# mag_mpu.net
KiCad netlist of a schematic drawn in Altium Designer
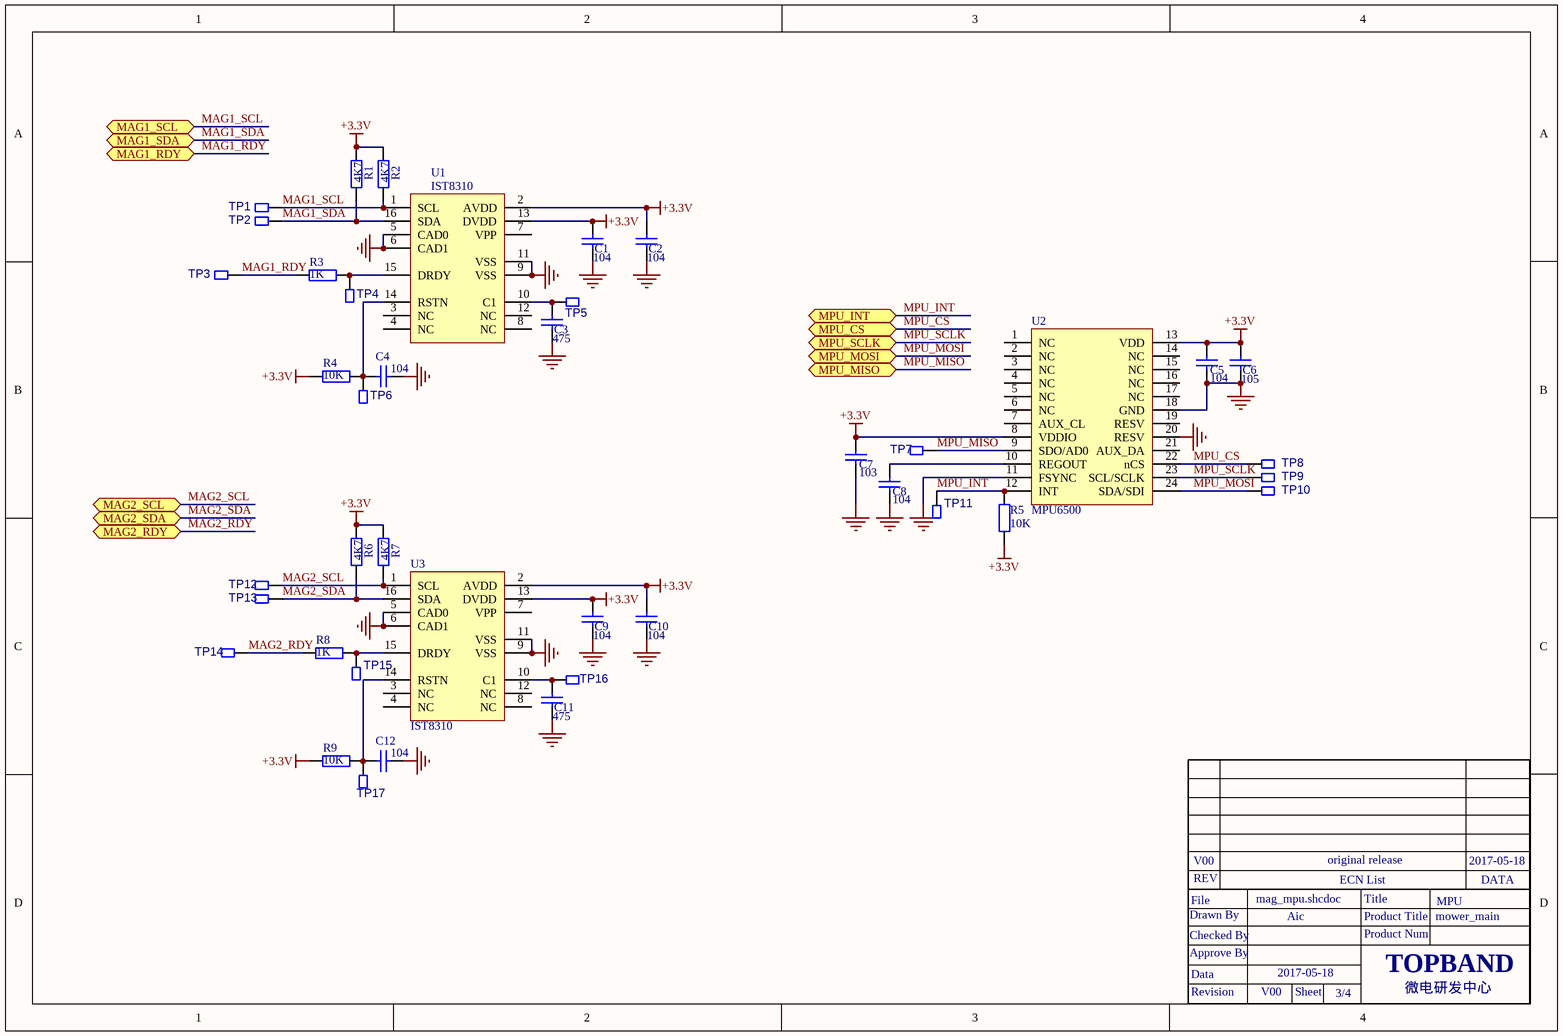
[diagram p0: mag_mpu.SchDoc]

(export (version "E")
  (design (tool "Eeschema 10.0.6"))
  (components
    (comp (ref "C1")
      (value "104")
      (footprint "0603C")
      (libsource (lib "altium-import") (part "root_1_Cap(0603)_"))
    )
    (comp (ref "C2")
      (value "104")
      (footprint "0603C")
      (libsource (lib "altium-import") (part "root_1_Cap(0603)_"))
    )
    (comp (ref "C3")
      (value "475")
      (footprint "0603C")
      (libsource (lib "altium-import") (part "root_1_Cap(0603)_"))
    )
    (comp (ref "C4")
      (value "104")
      (footprint "0603C")
      (libsource (lib "altium-import") (part "root_2_Cap(0603)_"))
    )
    (comp (ref "C5")
      (value "104")
      (footprint "0603C")
      (libsource (lib "altium-import") (part "root_1_Cap(0603)_"))
    )
    (comp (ref "C6")
      (value "105")
      (footprint "0603C")
      (libsource (lib "altium-import") (part "root_1_Cap(0603)_"))
    )
    (comp (ref "C7")
      (value "103")
      (footprint "0603C")
      (libsource (lib "altium-import") (part "root_1_Cap(0603)_"))
    )
    (comp (ref "C8")
      (value "104")
      (footprint "0603C")
      (libsource (lib "altium-import") (part "root_1_Cap(0603)_"))
    )
    (comp (ref "C9")
      (value "104")
      (footprint "0603C")
      (libsource (lib "altium-import") (part "root_1_Cap(0603)_"))
    )
    (comp (ref "C10")
      (value "104")
      (footprint "0603C")
      (libsource (lib "altium-import") (part "root_1_Cap(0603)_"))
    )
    (comp (ref "C11")
      (value "475")
      (footprint "0603C")
      (libsource (lib "altium-import") (part "root_1_Cap(0603)_"))
    )
    (comp (ref "C12")
      (value "104")
      (footprint "0603C")
      (libsource (lib "altium-import") (part "root_2_Cap(0603)_"))
    )
    (comp (ref "R1")
      (value "4K7")
      (footprint "0603R")
      (description "Resistor")
      (fields (field (name "PUBLISHER") "Altium Limited"))
      (libsource (lib "") (part "Res2_1"))
    )
    (comp (ref "R2")
      (value "4K7")
      (footprint "0603R")
      (description "Resistor")
      (fields (field (name "PUBLISHER") "Altium Limited"))
      (libsource (lib "") (part "Res2_1"))
    )
    (comp (ref "R3")
      (value "1K")
      (footprint "0603R")
      (description "Resistor")
      (fields (field (name "PUBLISHER") "Altium Limited"))
      (libsource (lib "Miscellaneous Devices") (part "Res2"))
    )
    (comp (ref "R4")
      (value "10K")
      (footprint "0603R")
      (description "Resistor")
      (fields (field (name "PUBLISHER") "Altium Limited"))
      (libsource (lib "") (part "Res2_2"))
    )
    (comp (ref "R5")
      (value "10K")
      (footprint "0603R")
      (description "Resistor")
      (fields (field (name "PUBLISHER") "Altium Limited"))
      (libsource (lib "") (part "Res2_3"))
    )
    (comp (ref "R6")
      (value "4K7")
      (footprint "0603R")
      (description "Resistor")
      (fields (field (name "PUBLISHER") "Altium Limited"))
      (libsource (lib "") (part "Res2_1"))
    )
    (comp (ref "R7")
      (value "4K7")
      (footprint "0603R")
      (description "Resistor")
      (fields (field (name "PUBLISHER") "Altium Limited"))
      (libsource (lib "") (part "Res2_1"))
    )
    (comp (ref "R8")
      (value "1K")
      (footprint "0603R")
      (description "Resistor")
      (fields (field (name "PUBLISHER") "Altium Limited"))
      (libsource (lib "Miscellaneous Devices") (part "Res2"))
    )
    (comp (ref "R9")
      (value "10K")
      (footprint "0603R")
      (description "Resistor")
      (fields (field (name "PUBLISHER") "Altium Limited"))
      (libsource (lib "") (part "Res2_2"))
    )
    (comp (ref "TP1") (value "TP") (footprint "TEST-0.8MM") (libsource (lib "Topband1") (part "TP")))
    (comp (ref "TP2") (value "TP") (footprint "TEST-0.8MM") (libsource (lib "Topband1") (part "TP")))
    (comp (ref "TP3") (value "TP") (footprint "TEST-0.8MM") (libsource (lib "Topband1") (part "TP")))
    (comp (ref "TP4") (value "TP") (footprint "TEST-0.8MM") (libsource (lib "Topband1") (part "TP")))
    (comp (ref "TP5") (value "TP") (footprint "TEST-0.8MM") (libsource (lib "Topband1") (part "TP")))
    (comp (ref "TP6") (value "TP") (footprint "TEST-0.8MM") (libsource (lib "Topband1") (part "TP")))
    (comp (ref "TP7") (value "TP") (footprint "TEST-0.8MM") (libsource (lib "Topband1") (part "TP")))
    (comp (ref "TP8") (value "TP") (footprint "TEST-0.8MM") (libsource (lib "Topband1") (part "TP")))
    (comp (ref "TP9") (value "TP") (footprint "TEST-0.8MM") (libsource (lib "Topband1") (part "TP")))
    (comp (ref "TP10") (value "TP") (footprint "TEST-0.8MM") (libsource (lib "Topband1") (part "TP")))
    (comp (ref "TP11") (value "TP") (footprint "TEST-0.8MM") (libsource (lib "Topband1") (part "TP")))
    (comp (ref "TP12") (value "TP") (footprint "TEST-0.8MM") (libsource (lib "Topband1") (part "TP")))
    (comp (ref "TP13") (value "TP") (footprint "TEST-0.8MM") (libsource (lib "Topband1") (part "TP")))
    (comp (ref "TP14") (value "TP") (footprint "TEST-0.8MM") (libsource (lib "Topband1") (part "TP")))
    (comp (ref "TP15") (value "TP") (footprint "TEST-0.8MM") (libsource (lib "Topband1") (part "TP")))
    (comp (ref "TP16") (value "TP") (footprint "TEST-0.8MM") (libsource (lib "Topband1") (part "TP")))
    (comp (ref "TP17") (value "TP") (footprint "TEST-0.8MM") (libsource (lib "Topband1") (part "TP")))
    (comp (ref "U1") (value "IST8310") (footprint "QFN16") (libsource (lib "Schlib1") (part "IST8310")))
    (comp (ref "U2") (value "MPU6500") (footprint "QFN24") (libsource (lib "Schlib1") (part "MPU6500")))
    (comp (ref "U3") (value "IST8310") (footprint "QFN16") (libsource (lib "Schlib1") (part "IST8310")))
  )
  (nets
    (net (code "1") (name "+3.3V") (class "Default")
      (node (ref "C1") (pin "2") (pinfunction "2_2") (pintype "passive"))
      (node (ref "C10") (pin "2") (pinfunction "2_2") (pintype "passive"))
      (node (ref "C2") (pin "2") (pinfunction "2_2") (pintype "passive"))
      (node (ref "C5") (pin "2") (pinfunction "2_2") (pintype "passive"))
      (node (ref "C6") (pin "2") (pinfunction "2_2") (pintype "passive"))
      (node (ref "C7") (pin "2") (pinfunction "2_2") (pintype "passive"))
      (node (ref "C9") (pin "2") (pinfunction "2_2") (pintype "passive"))
      (node (ref "R1") (pin "2") (pinfunction "2_2") (pintype "passive"))
      (node (ref "R2") (pin "2") (pinfunction "2_2") (pintype "passive"))
      (node (ref "R4") (pin "1") (pinfunction "1_1") (pintype "passive"))
      (node (ref "R5") (pin "2") (pinfunction "2_2") (pintype "passive"))
      (node (ref "R6") (pin "2") (pinfunction "2_2") (pintype "passive"))
      (node (ref "R7") (pin "2") (pinfunction "2_2") (pintype "passive"))
      (node (ref "R9") (pin "1") (pinfunction "1_1") (pintype "passive"))
      (node (ref "U1") (pin "13") (pinfunction "DVDD_13") (pintype "passive"))
      (node (ref "U1") (pin "2") (pinfunction "AVDD_2") (pintype "passive"))
      (node (ref "U2") (pin "13") (pinfunction "VDD_13") (pintype "passive"))
      (node (ref "U2") (pin "8") (pinfunction "VDDIO_8") (pintype "passive"))
      (node (ref "U3") (pin "13") (pinfunction "DVDD_13") (pintype "passive"))
      (node (ref "U3") (pin "2") (pinfunction "AVDD_2") (pintype "passive"))
    )
    (net (code "2") (name "/MAG1_RDY") (class "Default")
      (node (ref "R3") (pin "2") (pinfunction "2_2") (pintype "passive"))
      (node (ref "TP3") (pin "1") (pintype "passive"))
    )
    (net (code "3") (name "/MAG1_SCL") (class "Default")
      (node (ref "R2") (pin "1") (pinfunction "1_1") (pintype "passive"))
      (node (ref "TP1") (pin "1") (pintype "passive"))
      (node (ref "U1") (pin "1") (pinfunction "SCL_1") (pintype "passive"))
    )
    (net (code "4") (name "/MAG1_SDA") (class "Default")
      (node (ref "R1") (pin "1") (pinfunction "1_1") (pintype "passive"))
      (node (ref "TP2") (pin "1") (pintype "passive"))
      (node (ref "U1") (pin "16") (pinfunction "SDA_16") (pintype "passive"))
    )
    (net (code "5") (name "/MAG2_RDY") (class "Default")
      (node (ref "R8") (pin "2") (pinfunction "2_2") (pintype "passive"))
      (node (ref "TP14") (pin "1") (pintype "passive"))
    )
    (net (code "6") (name "/MAG2_SCL") (class "Default")
      (node (ref "R7") (pin "1") (pinfunction "1_1") (pintype "passive"))
      (node (ref "TP12") (pin "1") (pintype "passive"))
      (node (ref "U3") (pin "1") (pinfunction "SCL_1") (pintype "passive"))
    )
    (net (code "7") (name "/MAG2_SDA") (class "Default")
      (node (ref "R6") (pin "1") (pinfunction "1_1") (pintype "passive"))
      (node (ref "TP13") (pin "1") (pintype "passive"))
      (node (ref "U3") (pin "16") (pinfunction "SDA_16") (pintype "passive"))
    )
    (net (code "8") (name "/MPU_CS") (class "Default")
      (node (ref "TP8") (pin "1") (pintype "passive"))
      (node (ref "U2") (pin "22") (pinfunction "nCS_22") (pintype "passive"))
    )
    (net (code "9") (name "/MPU_INT") (class "Default")
      (node (ref "R5") (pin "1") (pinfunction "1_1") (pintype "passive"))
      (node (ref "TP11") (pin "1") (pintype "passive"))
      (node (ref "U2") (pin "12") (pinfunction "INT_12") (pintype "passive"))
    )
    (net (code "10") (name "/MPU_MISO") (class "Default")
      (node (ref "TP7") (pin "1") (pintype "passive"))
      (node (ref "U2") (pin "9") (pinfunction "SDO/AD0_9") (pintype "passive"))
    )
    (net (code "11") (name "/MPU_MOSI") (class "Default")
      (node (ref "TP10") (pin "1") (pintype "passive"))
      (node (ref "U2") (pin "24") (pinfunction "SDA/SDI_24") (pintype "passive"))
    )
    (net (code "12") (name "/MPU_SCLK") (class "Default")
      (node (ref "TP9") (pin "1") (pintype "passive"))
      (node (ref "U2") (pin "23") (pinfunction "SCL/SCLK_23") (pintype "passive"))
    )
    (net (code "13") (name "GND") (class "Default")
      (node (ref "C1") (pin "1") (pinfunction "1_1") (pintype "passive"))
      (node (ref "C10") (pin "1") (pinfunction "1_1") (pintype "passive"))
      (node (ref "C11") (pin "1") (pinfunction "1_1") (pintype "passive"))
      (node (ref "C12") (pin "1") (pinfunction "1_1") (pintype "passive"))
      (node (ref "C2") (pin "1") (pinfunction "1_1") (pintype "passive"))
      (node (ref "C3") (pin "1") (pinfunction "1_1") (pintype "passive"))
      (node (ref "C4") (pin "1") (pinfunction "1_1") (pintype "passive"))
      (node (ref "C5") (pin "1") (pinfunction "1_1") (pintype "passive"))
      (node (ref "C6") (pin "1") (pinfunction "1_1") (pintype "passive"))
      (node (ref "C7") (pin "1") (pinfunction "1_1") (pintype "passive"))
      (node (ref "C8") (pin "1") (pinfunction "1_1") (pintype "passive"))
      (node (ref "C9") (pin "1") (pinfunction "1_1") (pintype "passive"))
      (node (ref "U1") (pin "11") (pinfunction "VSS_11") (pintype "passive"))
      (node (ref "U1") (pin "5") (pinfunction "CAD0_5") (pintype "passive"))
      (node (ref "U1") (pin "6") (pinfunction "CAD1_6") (pintype "passive"))
      (node (ref "U1") (pin "9") (pinfunction "VSS_9") (pintype "passive"))
      (node (ref "U2") (pin "11") (pinfunction "FSYNC_11") (pintype "passive"))
      (node (ref "U2") (pin "18") (pinfunction "GND_18") (pintype "passive"))
      (node (ref "U2") (pin "20") (pinfunction "RESV_20") (pintype "passive"))
      (node (ref "U3") (pin "11") (pinfunction "VSS_11") (pintype "passive"))
      (node (ref "U3") (pin "5") (pinfunction "CAD0_5") (pintype "passive"))
      (node (ref "U3") (pin "6") (pinfunction "CAD1_6") (pintype "passive"))
      (node (ref "U3") (pin "9") (pinfunction "VSS_9") (pintype "passive"))
    )
    (net (code "14") (name "Net-(U1-C1)") (class "Default")
      (node (ref "C3") (pin "2") (pinfunction "2_2") (pintype "passive"))
      (node (ref "TP5") (pin "1") (pintype "passive"))
      (node (ref "U1") (pin "10") (pinfunction "C1_10") (pintype "passive"))
    )
    (net (code "15") (name "Net-(U1-DRDY)") (class "Default")
      (node (ref "R3") (pin "1") (pinfunction "1_1") (pintype "passive"))
      (node (ref "TP4") (pin "1") (pintype "passive"))
      (node (ref "U1") (pin "15") (pinfunction "DRDY_15") (pintype "passive"))
    )
    (net (code "16") (name "Net-(U1-RSTN)") (class "Default")
      (node (ref "C4") (pin "2") (pinfunction "2_2") (pintype "passive"))
      (node (ref "R4") (pin "2") (pinfunction "2_2") (pintype "passive"))
      (node (ref "TP6") (pin "1") (pintype "passive"))
      (node (ref "U1") (pin "14") (pinfunction "RSTN_14") (pintype "passive"))
    )
    (net (code "17") (name "Net-(U2-REGOUT)") (class "Default")
      (node (ref "C8") (pin "2") (pinfunction "2_2") (pintype "passive"))
      (node (ref "U2") (pin "10") (pinfunction "REGOUT_10") (pintype "passive"))
    )
    (net (code "18") (name "Net-(U3-C1)") (class "Default")
      (node (ref "C11") (pin "2") (pinfunction "2_2") (pintype "passive"))
      (node (ref "TP16") (pin "1") (pintype "passive"))
      (node (ref "U3") (pin "10") (pinfunction "C1_10") (pintype "passive"))
    )
    (net (code "19") (name "Net-(U3-DRDY)") (class "Default")
      (node (ref "R8") (pin "1") (pinfunction "1_1") (pintype "passive"))
      (node (ref "TP15") (pin "1") (pintype "passive"))
      (node (ref "U3") (pin "15") (pinfunction "DRDY_15") (pintype "passive"))
    )
    (net (code "20") (name "Net-(U3-RSTN)") (class "Default")
      (node (ref "C12") (pin "2") (pinfunction "2_2") (pintype "passive"))
      (node (ref "R9") (pin "2") (pinfunction "2_2") (pintype "passive"))
      (node (ref "TP17") (pin "1") (pintype "passive"))
      (node (ref "U3") (pin "14") (pinfunction "RSTN_14") (pintype "passive"))
    )
    (net (code "21") (name "unconnected-(U1-NC-Pad3)") (class "Default")
      (node (ref "U1") (pin "3") (pinfunction "NC_3") (pintype "passive"))
    )
    (net (code "22") (name "unconnected-(U1-NC-Pad4)") (class "Default")
      (node (ref "U1") (pin "4") (pinfunction "NC_4") (pintype "passive"))
    )
    (net (code "23") (name "unconnected-(U1-NC-Pad8)") (class "Default")
      (node (ref "U1") (pin "8") (pinfunction "NC_8") (pintype "passive"))
    )
    (net (code "24") (name "unconnected-(U1-NC-Pad12)") (class "Default")
      (node (ref "U1") (pin "12") (pinfunction "NC_12") (pintype "passive"))
    )
    (net (code "25") (name "unconnected-(U1-VPP-Pad7)") (class "Default")
      (node (ref "U1") (pin "7") (pinfunction "VPP_7") (pintype "passive"))
    )
    (net (code "26") (name "unconnected-(U2-AUX_CL-Pad7)") (class "Default")
      (node (ref "U2") (pin "7") (pinfunction "AUX_CL_7") (pintype "passive"))
    )
    (net (code "27") (name "unconnected-(U2-AUX_DA-Pad21)") (class "Default")
      (node (ref "U2") (pin "21") (pinfunction "AUX_DA_21") (pintype "passive"))
    )
    (net (code "28") (name "unconnected-(U2-NC-Pad1)") (class "Default")
      (node (ref "U2") (pin "1") (pinfunction "NC_1") (pintype "passive"))
    )
    (net (code "29") (name "unconnected-(U2-NC-Pad2)") (class "Default")
      (node (ref "U2") (pin "2") (pinfunction "NC_2") (pintype "passive"))
    )
    (net (code "30") (name "unconnected-(U2-NC-Pad3)") (class "Default")
      (node (ref "U2") (pin "3") (pinfunction "NC_3") (pintype "passive"))
    )
    (net (code "31") (name "unconnected-(U2-NC-Pad4)") (class "Default")
      (node (ref "U2") (pin "4") (pinfunction "NC_4") (pintype "passive"))
    )
    (net (code "32") (name "unconnected-(U2-NC-Pad5)") (class "Default")
      (node (ref "U2") (pin "5") (pinfunction "NC_5") (pintype "passive"))
    )
    (net (code "33") (name "unconnected-(U2-NC-Pad6)") (class "Default")
      (node (ref "U2") (pin "6") (pinfunction "NC_6") (pintype "passive"))
    )
    (net (code "34") (name "unconnected-(U2-NC-Pad14)") (class "Default")
      (node (ref "U2") (pin "14") (pinfunction "NC_14") (pintype "passive"))
    )
    (net (code "35") (name "unconnected-(U2-NC-Pad15)") (class "Default")
      (node (ref "U2") (pin "15") (pinfunction "NC_15") (pintype "passive"))
    )
    (net (code "36") (name "unconnected-(U2-NC-Pad16)") (class "Default")
      (node (ref "U2") (pin "16") (pinfunction "NC_16") (pintype "passive"))
    )
    (net (code "37") (name "unconnected-(U2-NC-Pad17)") (class "Default")
      (node (ref "U2") (pin "17") (pinfunction "NC_17") (pintype "passive"))
    )
    (net (code "38") (name "unconnected-(U2-RESV-Pad19)") (class "Default")
      (node (ref "U2") (pin "19") (pinfunction "RESV_19") (pintype "passive"))
    )
    (net (code "39") (name "unconnected-(U3-NC-Pad3)") (class "Default")
      (node (ref "U3") (pin "3") (pinfunction "NC_3") (pintype "passive"))
    )
    (net (code "40") (name "unconnected-(U3-NC-Pad4)") (class "Default")
      (node (ref "U3") (pin "4") (pinfunction "NC_4") (pintype "passive"))
    )
    (net (code "41") (name "unconnected-(U3-NC-Pad8)") (class "Default")
      (node (ref "U3") (pin "8") (pinfunction "NC_8") (pintype "passive"))
    )
    (net (code "42") (name "unconnected-(U3-NC-Pad12)") (class "Default")
      (node (ref "U3") (pin "12") (pinfunction "NC_12") (pintype "passive"))
    )
    (net (code "43") (name "unconnected-(U3-VPP-Pad7)") (class "Default")
      (node (ref "U3") (pin "7") (pinfunction "VPP_7") (pintype "passive"))
    )
  )
)
